# FM_module_TEA5767.net
KiCad netlist of a schematic drawn in EAGLE
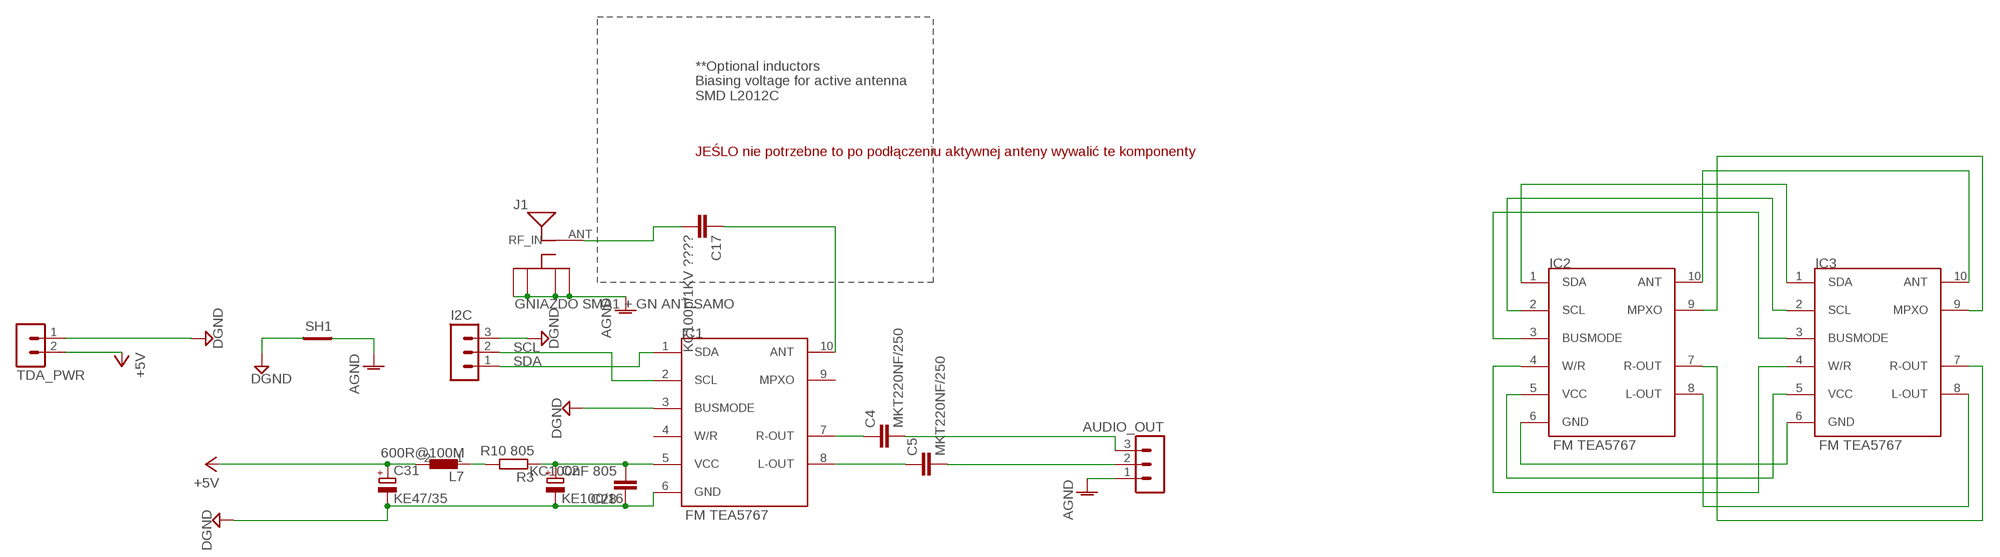
[diagram p0: schematic, sheet 1]

(export (version "E")
  (design (tool "Eeschema 10.0.6"))
  (components
    (comp (ref "AUDIO_OUT")
      (value "MA03-1")
      (footprint "eagle-import:MA03-1")
      (fields (field (name "OC_FARNELL") "unknown") (field (name "OC_NEWARK") "unknown"))
      (libsource (lib "eagle-import") (part "MA03-1"))
    )
    (comp (ref "C2")
      (value "KE100/16")
      (footprint "eagle-import:TT2D6")
      (libsource (lib "eagle-import") (part "CPOL-EUTT2D6"))
    )
    (comp (ref "C4")
      (value "MKT220NF/250")
      (footprint "eagle-import:C050-050X075")
      (libsource (lib "eagle-import") (part "C-EU050-050X075"))
    )
    (comp (ref "C5")
      (value "MKT220NF/250")
      (footprint "eagle-import:C050-050X075")
      (libsource (lib "eagle-import") (part "C-EU050-050X075"))
    )
    (comp (ref "C17")
      (value "KC100p/1KV ????")
      (footprint "eagle-import:C050-025X075")
      (libsource (lib "eagle-import") (part "C-EU050-025X075"))
    )
    (comp (ref "C28")
      (value "KC100nF 805")
      (footprint "eagle-import:C0805")
      (libsource (lib "eagle-import") (part "C-EUC0805"))
    )
    (comp (ref "C31")
      (value "KE47/35")
      (footprint "eagle-import:TT2D6")
      (libsource (lib "eagle-import") (part "CPOL-EUTT2D6"))
    )
    (comp (ref "I2C")
      (value "MA03-1")
      (footprint "eagle-import:MA03-1")
      (fields (field (name "OC_FARNELL") "unknown") (field (name "OC_NEWARK") "unknown"))
      (libsource (lib "eagle-import") (part "MA03-1"))
    )
    (comp (ref "IC1")
      (value "FM TEA5767")
      (footprint "eagle-import:PROTOTYPE")
      (libsource (lib "eagle-import") (part "TEA5767_MODULE_2.54MM"))
    )
    (comp (ref "IC2")
      (value "FM TEA5767")
      (footprint "eagle-import:PROTOTYPE")
      (libsource (lib "eagle-import") (part "TEA5767_MODULE_2.54MM"))
    )
    (comp (ref "IC3")
      (value "FM TEA5767")
      (footprint "eagle-import:SMD")
      (libsource (lib "eagle-import") (part "TEA5767_MODULE_SMD"))
    )
    (comp (ref "J1")
      (value "GNIAZDO SMA1 + GN ANT SAMO")
      (footprint "eagle-import:1053378-1")
      (libsource (lib "eagle-import") (part "J_SMA_TYCO_1053378"))
    )
    (comp (ref "L7")
      (value "600R@100M")
      (footprint "eagle-import:R0805")
      (libsource (lib "eagle-import") (part "FERRITR0805"))
    )
    (comp (ref "R3")
      (value "R10 805")
      (footprint "eagle-import:R0805")
      (libsource (lib "eagle-import") (part "R-EU_R0805"))
    )
    (comp (ref "SH1")
      (value "SHORT-HT5")
      (footprint "eagle-import:SHORT_TOP-50")
      (libsource (lib "eagle-import") (part "SHORT-HT5"))
    )
    (comp (ref "TDA_PWR")
      (value "MA02-1")
      (footprint "eagle-import:MA02-1")
      (libsource (lib "eagle-import") (part "MA02-1"))
    )
  )
  (nets
    (net (code "1") (name "+5V") (class "Default")
      (node (ref "C31") (pin "+") (pinfunction "+_+") (pintype "passive"))
      (node (ref "L7") (pin "2") (pinfunction "2_2") (pintype "passive"))
      (node (ref "TDA_PWR") (pin "2") (pinfunction "2_2") (pintype "passive"))
    )
    (net (code "2") (name "/SCL") (class "Default")
      (node (ref "I2C") (pin "2") (pinfunction "2_2") (pintype "passive"))
      (node (ref "IC1") (pin "2") (pinfunction "SCL_2") (pintype "bidirectional"))
    )
    (net (code "3") (name "/SDA") (class "Default")
      (node (ref "I2C") (pin "1") (pinfunction "1_1") (pintype "passive"))
      (node (ref "IC1") (pin "1") (pinfunction "SDA_1") (pintype "bidirectional"))
    )
    (net (code "4") (name "AGND") (class "Default")
      (node (ref "AUDIO_OUT") (pin "1") (pinfunction "1_1") (pintype "passive"))
      (node (ref "J1") (pin "GND_1") (pinfunction "RFGND_1_GND_1") (pintype "power_in"))
      (node (ref "J1") (pin "GND_2") (pinfunction "RFGND_2_GND_2") (pintype "power_in"))
      (node (ref "J1") (pin "GND_3") (pinfunction "RFGND_3_GND_3") (pintype "power_in"))
      (node (ref "J1") (pin "GND_4") (pinfunction "RFGND_4_GND_4") (pintype "power_in"))
      (node (ref "SH1") (pin "2") (pinfunction "P$2_2") (pintype "bidirectional"))
    )
    (net (code "5") (name "DGND") (class "Default")
      (node (ref "C2") (pin "-") (pinfunction "-_-") (pintype "passive"))
      (node (ref "C28") (pin "1") (pinfunction "1_1") (pintype "passive"))
      (node (ref "C31") (pin "-") (pinfunction "-_-") (pintype "passive"))
      (node (ref "I2C") (pin "3") (pinfunction "3_3") (pintype "passive"))
      (node (ref "IC1") (pin "3") (pinfunction "BUSMODE_3") (pintype "input"))
      (node (ref "IC1") (pin "6") (pinfunction "GND_6") (pintype "power_in"))
      (node (ref "SH1") (pin "1") (pinfunction "P$1_1") (pintype "bidirectional"))
      (node (ref "TDA_PWR") (pin "1") (pinfunction "1_1") (pintype "passive"))
    )
    (net (code "6") (name "Net-(AUDIO_OUT-Pad2)") (class "Default")
      (node (ref "AUDIO_OUT") (pin "2") (pinfunction "2_2") (pintype "passive"))
      (node (ref "C5") (pin "2") (pinfunction "2_2") (pintype "passive"))
    )
    (net (code "7") (name "Net-(AUDIO_OUT-Pad3)") (class "Default")
      (node (ref "AUDIO_OUT") (pin "3") (pinfunction "3_3") (pintype "passive"))
      (node (ref "C4") (pin "2") (pinfunction "2_2") (pintype "passive"))
    )
    (net (code "8") (name "Net-(IC1-ANT)") (class "Default")
      (node (ref "C17") (pin "1") (pinfunction "1_1") (pintype "passive"))
      (node (ref "IC1") (pin "10") (pinfunction "ANT_10") (pintype "input"))
    )
    (net (code "9") (name "Net-(IC1-L-OUT)") (class "Default")
      (node (ref "C5") (pin "1") (pinfunction "1_1") (pintype "passive"))
      (node (ref "IC1") (pin "8") (pinfunction "L-OUT_8") (pintype "output"))
    )
    (net (code "10") (name "Net-(IC1-R-OUT)") (class "Default")
      (node (ref "C4") (pin "1") (pinfunction "1_1") (pintype "passive"))
      (node (ref "IC1") (pin "7") (pinfunction "R-OUT_7") (pintype "output"))
    )
    (net (code "11") (name "Net-(IC1-VCC)") (class "Default")
      (node (ref "C2") (pin "+") (pinfunction "+_+") (pintype "passive"))
      (node (ref "C28") (pin "2") (pinfunction "2_2") (pintype "passive"))
      (node (ref "IC1") (pin "5") (pinfunction "VCC_5") (pintype "power_in"))
      (node (ref "R3") (pin "1") (pinfunction "1_1") (pintype "passive"))
    )
    (net (code "12") (name "Net-(IC2-ANT)") (class "Default")
      (node (ref "IC2") (pin "10") (pinfunction "ANT_10") (pintype "input"))
      (node (ref "IC3") (pin "10") (pinfunction "ANT_10") (pintype "input"))
    )
    (net (code "13") (name "Net-(IC2-BUSMODE)") (class "Default")
      (node (ref "IC2") (pin "3") (pinfunction "BUSMODE_3") (pintype "input"))
      (node (ref "IC3") (pin "3") (pinfunction "BUSMODE_3") (pintype "input"))
    )
    (net (code "14") (name "Net-(IC2-GND)") (class "Default")
      (node (ref "IC2") (pin "6") (pinfunction "GND_6") (pintype "power_in"))
      (node (ref "IC3") (pin "6") (pinfunction "GND_6") (pintype "power_in"))
    )
    (net (code "15") (name "Net-(IC2-L-OUT)") (class "Default")
      (node (ref "IC2") (pin "8") (pinfunction "L-OUT_8") (pintype "output"))
      (node (ref "IC3") (pin "8") (pinfunction "L-OUT_8") (pintype "output"))
    )
    (net (code "16") (name "Net-(IC2-MPXO)") (class "Default")
      (node (ref "IC2") (pin "9") (pinfunction "MPXO_9") (pintype "output"))
      (node (ref "IC3") (pin "9") (pinfunction "MPXO_9") (pintype "output"))
    )
    (net (code "17") (name "Net-(IC2-R-OUT)") (class "Default")
      (node (ref "IC2") (pin "7") (pinfunction "R-OUT_7") (pintype "output"))
      (node (ref "IC3") (pin "7") (pinfunction "R-OUT_7") (pintype "output"))
    )
    (net (code "18") (name "Net-(IC2-SCL)") (class "Default")
      (node (ref "IC2") (pin "2") (pinfunction "SCL_2") (pintype "bidirectional"))
      (node (ref "IC3") (pin "2") (pinfunction "SCL_2") (pintype "bidirectional"))
    )
    (net (code "19") (name "Net-(IC2-SDA)") (class "Default")
      (node (ref "IC2") (pin "1") (pinfunction "SDA_1") (pintype "bidirectional"))
      (node (ref "IC3") (pin "1") (pinfunction "SDA_1") (pintype "bidirectional"))
    )
    (net (code "20") (name "Net-(IC2-VCC)") (class "Default")
      (node (ref "IC2") (pin "5") (pinfunction "VCC_5") (pintype "power_in"))
      (node (ref "IC3") (pin "5") (pinfunction "VCC_5") (pintype "power_in"))
    )
    (net (code "21") (name "Net-(IC2-W{slash}R)") (class "Default")
      (node (ref "IC2") (pin "4") (pinfunction "W/R_4") (pintype "input"))
      (node (ref "IC3") (pin "4") (pinfunction "W/R_4") (pintype "input"))
    )
    (net (code "22") (name "Net-(J1-RF_IN)") (class "Default")
      (node (ref "C17") (pin "2") (pinfunction "2_2") (pintype "passive"))
      (node (ref "J1") (pin "ANT") (pinfunction "RF_IN_ANT") (pintype "input"))
    )
    (net (code "23") (name "Net-(L7-Pad1)") (class "Default")
      (node (ref "L7") (pin "1") (pinfunction "1_1") (pintype "passive"))
      (node (ref "R3") (pin "2") (pinfunction "2_2") (pintype "passive"))
    )
    (net (code "24") (name "unconnected-(IC1-MPXO-Pad9)") (class "Default")
      (node (ref "IC1") (pin "9") (pinfunction "MPXO_9") (pintype "output"))
    )
    (net (code "25") (name "unconnected-(IC1-W{slash}R-Pad4)") (class "Default")
      (node (ref "IC1") (pin "4") (pinfunction "W/R_4") (pintype "input"))
    )
  )
)
